# scanner-ale.net
KiCad netlist of a schematic drawn in EAGLE
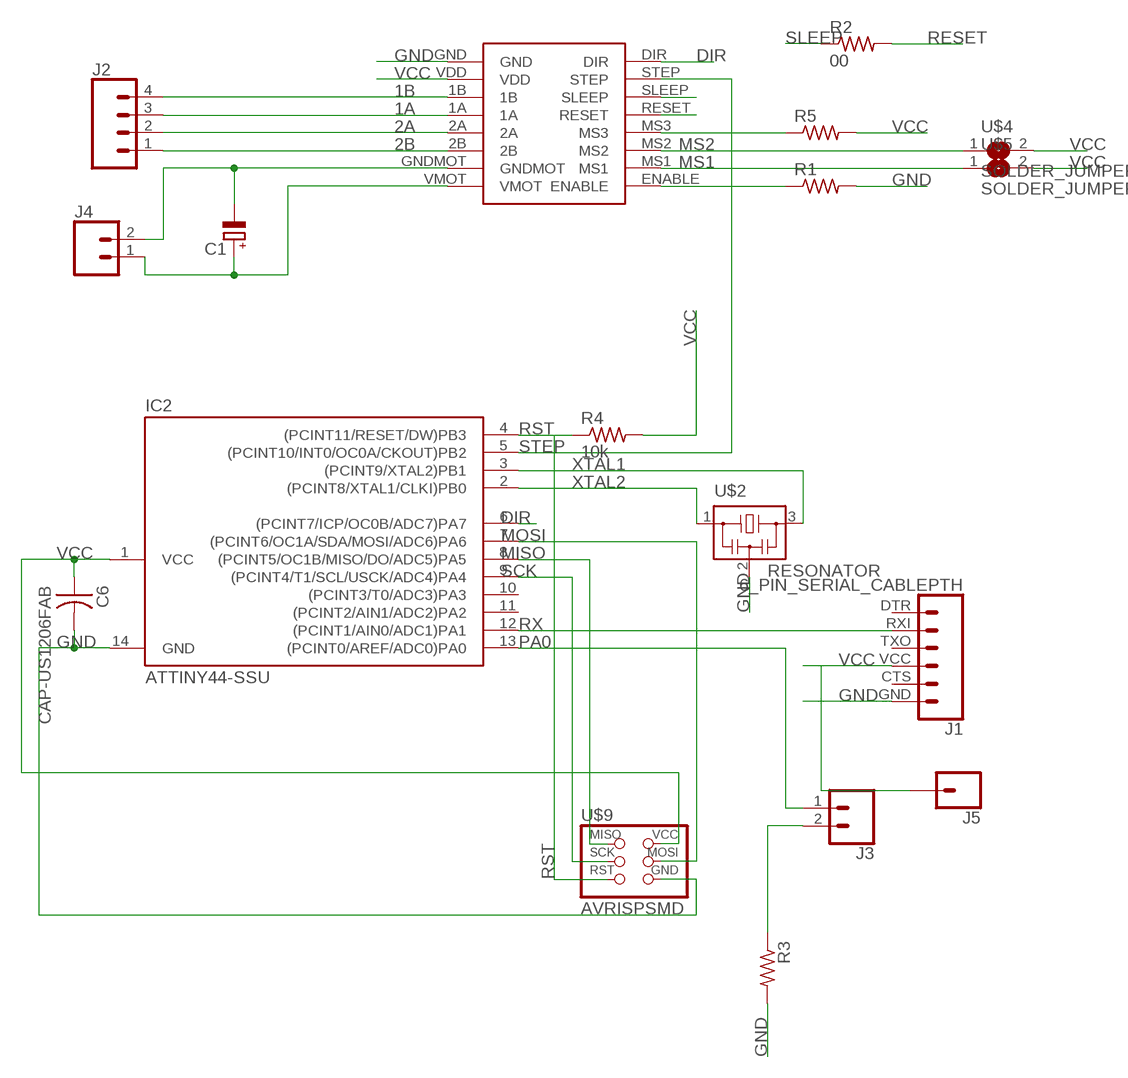
[diagram p0: schematic, sheet 1]

(export (version "E")
  (design (tool "Eeschema 10.0.6"))
  (components
    (comp (ref "C1")
      (value "CPOL-EUE2,5-6E")
      (footprint "eagle-import:E2,5-6E")
      (libsource (lib "eagle-import") (part "CPOL-EUE2,5-6E"))
    )
    (comp (ref "C6")
      (value "CAP-US1206FAB")
      (footprint "eagle-import:C1206FAB")
      (libsource (lib "eagle-import") (part "CAP-US1206FAB"))
    )
    (comp (ref "IC2")
      (value "ATTINY44-SSU")
      (footprint "eagle-import:SOIC14")
      (libsource (lib "eagle-import") (part "ATTINY44-SSU"))
    )
    (comp (ref "J1")
      (value "6_PIN_SERIAL_CABLEPTH")
      (footprint "eagle-import:FTDI_BASIC")
      (libsource (lib "eagle-import") (part "6_PIN_SERIAL_CABLEPTH"))
    )
    (comp (ref "J2")
      (value "CONN_04")
      (footprint "eagle-import:1X04")
      (libsource (lib "eagle-import") (part "CONN_04"))
    )
    (comp (ref "J3")
      (value "CONN_02")
      (footprint "eagle-import:1X02")
      (libsource (lib "eagle-import") (part "CONN_02"))
    )
    (comp (ref "J4")
      (value "CONN_02")
      (footprint "eagle-import:1X02")
      (libsource (lib "eagle-import") (part "CONN_02"))
    )
    (comp (ref "J5")
      (value "CONN_01")
      (footprint "eagle-import:1X01")
      (libsource (lib "eagle-import") (part "CONN_01"))
    )
    (comp (ref "R1")
      (value "RES-US1206FAB")
      (footprint "eagle-import:R1206FAB")
      (libsource (lib "eagle-import") (part "RES-US1206FAB"))
    )
    (comp (ref "R2")
      (value "00")
      (footprint "eagle-import:R1206FAB")
      (libsource (lib "eagle-import") (part "RES-US1206FAB"))
    )
    (comp (ref "R3")
      (value "RES-US1206FAB")
      (footprint "eagle-import:R1206FAB")
      (libsource (lib "eagle-import") (part "RES-US1206FAB"))
    )
    (comp (ref "R4")
      (value "10k")
      (footprint "eagle-import:R1206FAB")
      (libsource (lib "eagle-import") (part "RES-US1206FAB"))
    )
    (comp (ref "R5")
      (value "RES-US1206FAB")
      (footprint "eagle-import:R1206FAB")
      (libsource (lib "eagle-import") (part "RES-US1206FAB"))
    )
    (comp (ref "U$1")
      (value "POLOLUESTEPPERDRIVERDIL16MAT")
      (footprint "eagle-import:DIL16")
      (libsource (lib "eagle-import") (part "POLOLUESTEPPERDRIVERDIL16MAT"))
    )
    (comp (ref "U$2")
      (value "RESONATOR")
      (footprint "eagle-import:EFOBM")
      (libsource (lib "eagle-import") (part "RESONATOR"))
    )
    (comp (ref "U$4")
      (value "SOLDER_JUMPER")
      (footprint "eagle-import:SJFAB")
      (libsource (lib "eagle-import") (part "SOLDER_JUMPER"))
    )
    (comp (ref "U$5")
      (value "SOLDER_JUMPER")
      (footprint "eagle-import:SJFAB")
      (libsource (lib "eagle-import") (part "SOLDER_JUMPER"))
    )
    (comp (ref "U$9")
      (value "AVRISPSMD")
      (footprint "eagle-import:2X03SMD")
      (libsource (lib "eagle-import") (part "AVRISPSMD"))
    )
  )
  (nets
    (net (code "1") (name "/1A") (class "Default")
      (node (ref "J2") (pin "3") (pinfunction "3_3") (pintype "passive"))
      (node (ref "U$1") (pin "1A") (pinfunction "1A_1A") (pintype "output"))
    )
    (net (code "2") (name "/1B") (class "Default")
      (node (ref "J2") (pin "4") (pinfunction "4_4") (pintype "passive"))
      (node (ref "U$1") (pin "1B") (pinfunction "1B_1B") (pintype "output"))
    )
    (net (code "3") (name "/2A") (class "Default")
      (node (ref "J2") (pin "2") (pinfunction "2_2") (pintype "passive"))
      (node (ref "U$1") (pin "2A") (pinfunction "2A_2A") (pintype "output"))
    )
    (net (code "4") (name "/2B") (class "Default")
      (node (ref "J2") (pin "1") (pinfunction "1_1") (pintype "passive"))
      (node (ref "U$1") (pin "2B") (pinfunction "2B_2B") (pintype "output"))
    )
    (net (code "5") (name "/DIR") (class "Default")
      (node (ref "IC2") (pin "6") (pinfunction "(PCINT7/ICP/OC0B/ADC7)PA7_6") (pintype "bidirectional"))
      (node (ref "U$1") (pin "DIR") (pinfunction "DIR_DIR") (pintype "input"))
    )
    (net (code "6") (name "/GND") (class "Default")
      (node (ref "C6") (pin "2") (pinfunction "2_2") (pintype "passive"))
      (node (ref "IC2") (pin "14") (pinfunction "GND_14") (pintype "power_in"))
      (node (ref "J1") (pin "GND") (pinfunction "6_GND") (pintype "passive"))
      (node (ref "R1") (pin "2") (pinfunction "2_2") (pintype "passive"))
      (node (ref "R3") (pin "2") (pinfunction "2_2") (pintype "passive"))
      (node (ref "U$1") (pin "GND") (pinfunction "GND_GND") (pintype "power_in"))
      (node (ref "U$2") (pin "2") (pinfunction "2_2") (pintype "passive"))
      (node (ref "U$9") (pin "6") (pinfunction "GND_6") (pintype "passive"))
    )
    (net (code "7") (name "/MISO") (class "Default")
      (node (ref "IC2") (pin "8") (pinfunction "(PCINT5/OC1B/MISO/DO/ADC5)PA5_8") (pintype "bidirectional"))
      (node (ref "U$9") (pin "1") (pinfunction "MISO_1") (pintype "passive"))
    )
    (net (code "8") (name "/MOSI") (class "Default")
      (node (ref "IC2") (pin "7") (pinfunction "(PCINT6/OC1A/SDA/MOSI/ADC6)PA6_7") (pintype "bidirectional"))
      (node (ref "U$9") (pin "4") (pinfunction "MOSI_4") (pintype "passive"))
    )
    (net (code "9") (name "/MS1") (class "Default")
      (node (ref "U$1") (pin "MS1") (pinfunction "MS1_MS1") (pintype "input"))
      (node (ref "U$5") (pin "1") (pinfunction "1_1") (pintype "passive"))
    )
    (net (code "10") (name "/MS2") (class "Default")
      (node (ref "U$1") (pin "MS2") (pinfunction "MS2_MS2") (pintype "input"))
      (node (ref "U$4") (pin "1") (pinfunction "1_1") (pintype "passive"))
    )
    (net (code "11") (name "/PA0") (class "Default")
      (node (ref "IC2") (pin "13") (pinfunction "(PCINT0/AREF/ADC0)PA0_13") (pintype "bidirectional"))
      (node (ref "J3") (pin "1") (pinfunction "1_1") (pintype "passive"))
    )
    (net (code "12") (name "/RESET") (class "Default")
      (node (ref "R2") (pin "2") (pinfunction "2_2") (pintype "passive"))
      (node (ref "U$1") (pin "RESET") (pinfunction "RESET_RESET") (pintype "input"))
    )
    (net (code "13") (name "/RST") (class "Default")
      (node (ref "IC2") (pin "4") (pinfunction "(PCINT11/RESET/DW)PB3_4") (pintype "bidirectional"))
      (node (ref "R4") (pin "1") (pinfunction "1_1") (pintype "passive"))
      (node (ref "U$9") (pin "5") (pinfunction "RST_5") (pintype "passive"))
    )
    (net (code "14") (name "/RX") (class "Default")
      (node (ref "IC2") (pin "12") (pinfunction "(PCINT1/AIN0/ADC1)PA1_12") (pintype "bidirectional"))
      (node (ref "J1") (pin "RXI") (pinfunction "2_RXI") (pintype "passive"))
    )
    (net (code "15") (name "/SCK") (class "Default")
      (node (ref "IC2") (pin "9") (pinfunction "(PCINT4/T1/SCL/USCK/ADC4)PA4_9") (pintype "bidirectional"))
      (node (ref "U$9") (pin "3") (pinfunction "SCK_3") (pintype "passive"))
    )
    (net (code "16") (name "/SLEEP") (class "Default")
      (node (ref "R2") (pin "1") (pinfunction "1_1") (pintype "passive"))
      (node (ref "U$1") (pin "SLEEP") (pinfunction "SLEEP_SLEEP") (pintype "input"))
    )
    (net (code "17") (name "/STEP") (class "Default")
      (node (ref "IC2") (pin "5") (pinfunction "(PCINT10/INT0/OC0A/CKOUT)PB2_5") (pintype "bidirectional"))
      (node (ref "U$1") (pin "STEP") (pinfunction "STEP_STEP") (pintype "input"))
    )
    (net (code "18") (name "/VCC") (class "Default")
      (node (ref "C6") (pin "1") (pinfunction "1_1") (pintype "passive"))
      (node (ref "IC2") (pin "1") (pinfunction "VCC_1") (pintype "power_in"))
      (node (ref "J1") (pin "VCC") (pinfunction "4_VCC") (pintype "passive"))
      (node (ref "J5") (pin "1") (pinfunction "1_1") (pintype "passive"))
      (node (ref "R4") (pin "2") (pinfunction "2_2") (pintype "passive"))
      (node (ref "R5") (pin "2") (pinfunction "2_2") (pintype "passive"))
      (node (ref "U$1") (pin "VDD") (pinfunction "VDD_VDD") (pintype "power_in"))
      (node (ref "U$4") (pin "2") (pinfunction "2_2") (pintype "passive"))
      (node (ref "U$5") (pin "2") (pinfunction "2_2") (pintype "passive"))
      (node (ref "U$9") (pin "2") (pinfunction "VCC_2") (pintype "passive"))
    )
    (net (code "19") (name "/XTAL1") (class "Default")
      (node (ref "IC2") (pin "3") (pinfunction "(PCINT9/XTAL2)PB1_3") (pintype "bidirectional"))
      (node (ref "U$2") (pin "3") (pinfunction "3_3") (pintype "passive"))
    )
    (net (code "20") (name "/XTAL2") (class "Default")
      (node (ref "IC2") (pin "2") (pinfunction "(PCINT8/XTAL1/CLKI)PB0_2") (pintype "bidirectional"))
      (node (ref "U$2") (pin "1") (pinfunction "1_1") (pintype "passive"))
    )
    (net (code "21") (name "Net-(C1-Pad+)") (class "Default")
      (node (ref "C1") (pin "+") (pinfunction "+_+") (pintype "passive"))
      (node (ref "J4") (pin "1") (pinfunction "1_1") (pintype "passive"))
      (node (ref "U$1") (pin "VMOT") (pinfunction "VMOT_VMOT") (pintype "power_in"))
    )
    (net (code "22") (name "Net-(C1-Pad-)") (class "Default")
      (node (ref "C1") (pin "-") (pinfunction "-_-") (pintype "passive"))
      (node (ref "J4") (pin "2") (pinfunction "2_2") (pintype "passive"))
      (node (ref "U$1") (pin "GNDMOT") (pinfunction "GNDMOT_GNDMOT") (pintype "power_in"))
    )
    (net (code "23") (name "Net-(J3-Pad2)") (class "Default")
      (node (ref "J3") (pin "2") (pinfunction "2_2") (pintype "passive"))
      (node (ref "R3") (pin "1") (pinfunction "1_1") (pintype "passive"))
    )
    (net (code "24") (name "Net-(R1-Pad1)") (class "Default")
      (node (ref "R1") (pin "1") (pinfunction "1_1") (pintype "passive"))
      (node (ref "U$1") (pin "ENABLE") (pinfunction "ENABLE_ENABLE") (pintype "input"))
    )
    (net (code "25") (name "Net-(R5-Pad1)") (class "Default")
      (node (ref "R5") (pin "1") (pinfunction "1_1") (pintype "passive"))
      (node (ref "U$1") (pin "MS3") (pinfunction "MS3_MS3") (pintype "input"))
    )
    (net (code "26") (name "unconnected-(IC2-(PCINT2{slash}AIN1{slash}ADC2)PA2-Pad11)") (class "Default")
      (node (ref "IC2") (pin "11") (pinfunction "(PCINT2/AIN1/ADC2)PA2_11") (pintype "bidirectional"))
    )
    (net (code "27") (name "unconnected-(IC2-(PCINT3{slash}T0{slash}ADC3)PA3-Pad10)") (class "Default")
      (node (ref "IC2") (pin "10") (pinfunction "(PCINT3/T0/ADC3)PA3_10") (pintype "bidirectional"))
    )
    (net (code "28") (name "unconnected-(J1-1-PadDTR)") (class "Default")
      (node (ref "J1") (pin "DTR") (pinfunction "1_DTR") (pintype "passive"))
    )
    (net (code "29") (name "unconnected-(J1-3-PadTXO)") (class "Default")
      (node (ref "J1") (pin "TXO") (pinfunction "3_TXO") (pintype "passive"))
    )
    (net (code "30") (name "unconnected-(J1-5-PadCTS)") (class "Default")
      (node (ref "J1") (pin "CTS") (pinfunction "5_CTS") (pintype "passive"))
    )
  )
)
